# MCU_Connections.net
KiCad netlist of a schematic drawn in Altium Designer
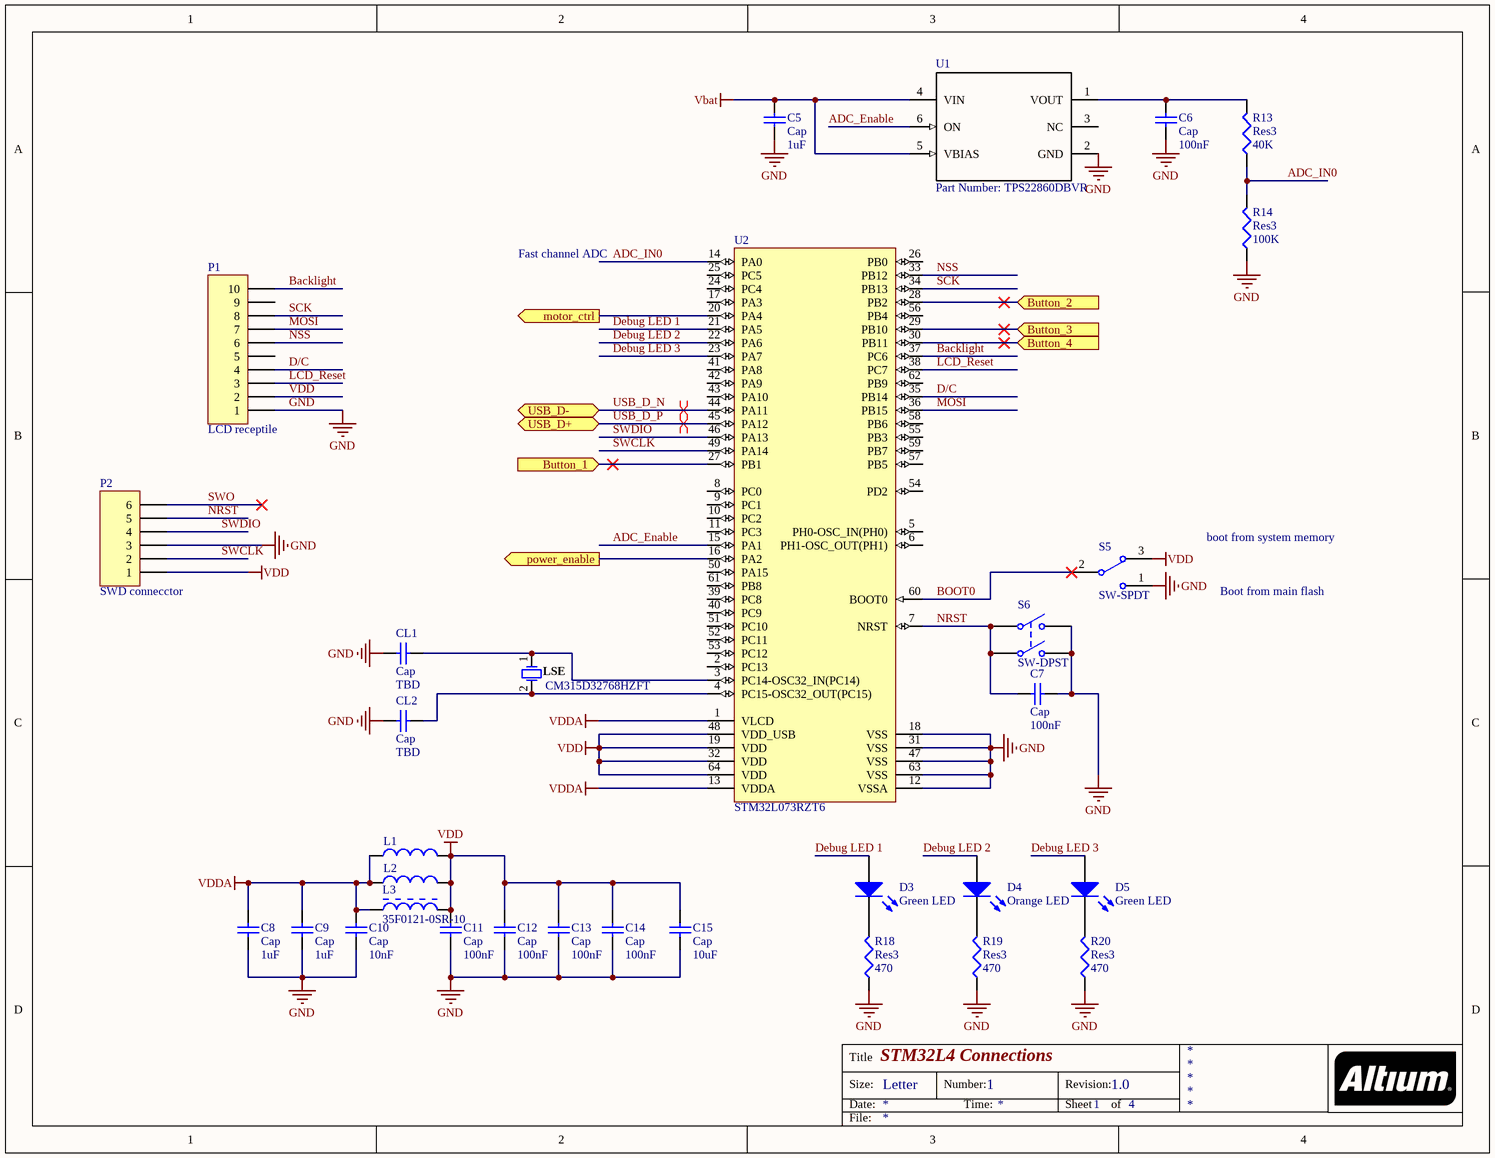
[diagram p0: MCU_Connections.SchDoc]

(export (version "E")
  (design (tool "Eeschema 10.0.6"))
  (components
    (comp (ref "C5")
      (value "Cap")
      (footprint "C0805")
      (description "Capacitor")
      (fields (field (name "ALTIUM_VALUE") "1uF") (field (name "PUBLISHER") "Altium Limited"))
      (libsource (lib "Miscellaneous Devices") (part "Cap"))
    )
    (comp (ref "C6")
      (value "Cap")
      (footprint "C0805")
      (description "Capacitor")
      (fields (field (name "ALTIUM_VALUE") "100nF") (field (name "PUBLISHER") "Altium Limited"))
      (libsource (lib "Miscellaneous Devices") (part "Cap"))
    )
    (comp (ref "C7")
      (value "Cap")
      (footprint "C0805")
      (description "Capacitor")
      (fields (field (name "ALTIUM_VALUE") "100nF") (field (name "PUBLISHER") "Altium Limited"))
      (libsource (lib "Miscellaneous Devices") (part "Cap"))
    )
    (comp (ref "C8")
      (value "Cap")
      (footprint "C0805")
      (description "Capacitor")
      (fields (field (name "ALTIUM_VALUE") "1uF") (field (name "PUBLISHER") "Altium Limited"))
      (libsource (lib "Miscellaneous Devices") (part "Cap"))
    )
    (comp (ref "C9")
      (value "Cap")
      (footprint "C0805")
      (description "Capacitor")
      (fields (field (name "ALTIUM_VALUE") "1uF") (field (name "PUBLISHER") "Altium Limited"))
      (libsource (lib "Miscellaneous Devices") (part "Cap"))
    )
    (comp (ref "C10")
      (value "Cap")
      (footprint "C0805")
      (description "Capacitor")
      (fields (field (name "ALTIUM_VALUE") "10nF") (field (name "PUBLISHER") "Altium Limited"))
      (libsource (lib "Miscellaneous Devices") (part "Cap"))
    )
    (comp (ref "C11")
      (value "Cap")
      (footprint "C0805")
      (description "Capacitor")
      (fields (field (name "ALTIUM_VALUE") "100nF") (field (name "PUBLISHER") "Altium Limited"))
      (libsource (lib "Miscellaneous Devices") (part "Cap"))
    )
    (comp (ref "C12")
      (value "Cap")
      (footprint "C0805")
      (description "Capacitor")
      (fields (field (name "ALTIUM_VALUE") "100nF") (field (name "PUBLISHER") "Altium Limited"))
      (libsource (lib "Miscellaneous Devices") (part "Cap"))
    )
    (comp (ref "C13")
      (value "Cap")
      (footprint "C0805")
      (description "Capacitor")
      (fields (field (name "ALTIUM_VALUE") "100nF") (field (name "PUBLISHER") "Altium Limited"))
      (libsource (lib "Miscellaneous Devices") (part "Cap"))
    )
    (comp (ref "C14")
      (value "Cap")
      (footprint "C0805")
      (description "Capacitor")
      (fields (field (name "ALTIUM_VALUE") "100nF") (field (name "PUBLISHER") "Altium Limited"))
      (libsource (lib "Miscellaneous Devices") (part "Cap"))
    )
    (comp (ref "C15")
      (value "Cap")
      (footprint "C0805")
      (description "Capacitor")
      (fields (field (name "ALTIUM_VALUE") "10uF") (field (name "PUBLISHER") "Altium Limited"))
      (libsource (lib "Miscellaneous Devices") (part "Cap"))
    )
    (comp (ref "CL1")
      (value "Cap")
      (footprint "C0805")
      (description "Capacitor")
      (fields (field (name "ALTIUM_VALUE") "TBD") (field (name "PUBLISHER") "Altium Limited"))
      (libsource (lib "Miscellaneous Devices") (part "Cap"))
    )
    (comp (ref "CL2")
      (value "Cap")
      (footprint "C0805")
      (description "Capacitor")
      (fields (field (name "ALTIUM_VALUE") "TBD") (field (name "PUBLISHER") "Altium Limited"))
      (libsource (lib "Miscellaneous Devices") (part "Cap"))
    )
    (comp (ref "D3")
      (value "Green LED")
      (footprint "3.2X1.6X1.1")
      (description "Typical RED, GREEN, YELLOW, AMBER GaAs LED")
      (fields (field (name "PUBLISHER") "Altium Limited"))
      (libsource (lib "Miscellaneous Devices") (part "LED2"))
    )
    (comp (ref "D4")
      (value "Orange LED")
      (footprint "3.2X1.6X1.1")
      (description "Typical RED, GREEN, YELLOW, AMBER GaAs LED")
      (fields (field (name "PUBLISHER") "Altium Limited"))
      (libsource (lib "Miscellaneous Devices") (part "LED2"))
    )
    (comp (ref "D5")
      (value "Green LED")
      (footprint "3.2X1.6X1.1")
      (description "Typical RED, GREEN, YELLOW, AMBER GaAs LED")
      (fields (field (name "PUBLISHER") "Altium Limited"))
      (libsource (lib "Miscellaneous Devices") (part "LED2"))
    )
    (comp (ref "L1")
      (value "~")
      (footprint "C0805")
      (description "Inductor")
      (fields (field (name "PUBLISHER") "Altium Limited"))
      (libsource (lib "Miscellaneous Devices") (part "Inductor"))
    )
    (comp (ref "L2")
      (value "~")
      (footprint "C1206")
      (description "Inductor")
      (fields (field (name "PUBLISHER") "Altium Limited"))
      (libsource (lib "Miscellaneous Devices") (part "Inductor"))
    )
    (comp (ref "L3")
      (value "35F0121-0SR-10")
      (footprint "LIRD-35F0121-0SR-10_V")
      (description "EMI Filtering & RF Inductor, 10 A, 0.75 mOhm, -40 to 125 degC, 2-Pin SMD, RoHS, Tape and Reel")
      (fields (field (name "MANUFACTURER") "Laird"))
      (libsource (lib "Altium Content Vault") (part "IND-FB-2"))
    )
    (comp (ref "LSE")
      (value "CM315D32768HZFT")
      (footprint "CMHT-CM315D-2_V")
      (fields (field (name "MANUFACTURER") "Citizen Micro HumanTech"))
      (libsource (lib "Altium Content Vault") (part "XTAL-1-2-2"))
    )
    (comp (ref "P1")
      (value "LCD receptile")
      (footprint "HDR1X10")
      (description "Header, 10-Pin")
      (fields (field (name "PUBLISHER") "Altium Limited"))
      (libsource (lib "Miscellaneous Connectors") (part "Header 10"))
    )
    (comp (ref "P2")
      (value "SWD connecctor")
      (footprint "HDR1X6")
      (description "Header, 6-Pin")
      (fields (field (name "PUBLISHER") "Altium Limited"))
      (libsource (lib "Miscellaneous Connectors") (part "Header 6"))
    )
    (comp (ref "R13")
      (value "Res3")
      (footprint "1608[0603]")
      (description "Resistor")
      (fields (field (name "ALTIUM_VALUE") "40K") (field (name "PUBLISHER") "Altium Limited"))
      (libsource (lib "Miscellaneous Devices") (part "Res3"))
    )
    (comp (ref "R14")
      (value "Res3")
      (footprint "1608[0603]")
      (description "Resistor")
      (fields (field (name "ALTIUM_VALUE") "100K") (field (name "PUBLISHER") "Altium Limited"))
      (libsource (lib "Miscellaneous Devices") (part "Res3"))
    )
    (comp (ref "R18")
      (value "Res3")
      (footprint "1608[0603]")
      (description "Resistor")
      (fields (field (name "ALTIUM_VALUE") "470") (field (name "PUBLISHER") "Altium Limited"))
      (libsource (lib "Miscellaneous Devices") (part "Res3"))
    )
    (comp (ref "R19")
      (value "Res3")
      (footprint "1608[0603]")
      (description "Resistor")
      (fields (field (name "ALTIUM_VALUE") "470") (field (name "PUBLISHER") "Altium Limited"))
      (libsource (lib "Miscellaneous Devices") (part "Res3"))
    )
    (comp (ref "R20")
      (value "Res3")
      (footprint "1608[0603]")
      (description "Resistor")
      (fields (field (name "ALTIUM_VALUE") "470") (field (name "PUBLISHER") "Altium Limited"))
      (libsource (lib "Miscellaneous Devices") (part "Res3"))
    )
    (comp (ref "S5")
      (value "SW-SPDT")
      (footprint "HDR1X3")
      (description "SPDT Subminiature Toggle Switch, Right Angle Mounting, Vertical Actuation")
      (fields (field (name "PUBLISHER") "Altium Limited"))
      (libsource (lib "Miscellaneous Devices") (part "SW-SPDT"))
    )
    (comp (ref "S6")
      (value "SW-DPST")
      (footprint "PCBComponent_1")
      (description "Double-Pole, Single-Throw Switch")
      (fields (field (name "PUBLISHER") "Altium Limited"))
      (libsource (lib "Miscellaneous Devices") (part "SW-DPST"))
    )
    (comp (ref "U1")
      (value "Part Number: TPS22860DBVR")
      (footprint "DBV0006A_N")
      (description "No Description Available")
      (fields
        (field (name "MANUFACTURER_PART_NUMBER") "TPS22860DBVR")
        (field (name "MANUFACTURER") "Texas Instruments")
        (field (name "COPYRIGHT") "Copyright (C) 2018 Accelerated Designs. All rights reserved")
      )
      (libsource (lib "TI-TPS22860DBVR") (part "TPS22860DBVR"))
    )
    (comp (ref "U2")
      (value "STM32L073RZT6")
      (footprint "STM-LQFP64_M")
      (libsource (lib "Altium Content Vault") (part "MC-ARM-STM32L073-LQFP64"))
    )
  )
  (nets
    (net (code "1") (name "/ADC_Enable") (class "Default")
      (node (ref "U1") (pin "6") (pinfunction "ON_6") (pintype "input"))
      (node (ref "U2") (pin "15") (pinfunction "PA1_15") (pintype "bidirectional"))
    )
    (net (code "2") (name "/ADC_IN0") (class "Default")
      (node (ref "R13") (pin "1") (pinfunction "1_1") (pintype "passive"))
      (node (ref "R14") (pin "2") (pinfunction "2_2") (pintype "passive"))
      (node (ref "U2") (pin "14") (pinfunction "PA0_14") (pintype "bidirectional"))
    )
    (net (code "3") (name "/BOOT0") (class "Default")
      (node (ref "S5") (pin "2") (pinfunction "2_2") (pintype "passive"))
      (node (ref "U2") (pin "60") (pinfunction "BOOT0_60") (pintype "input"))
    )
    (net (code "4") (name "/Backlight") (class "Default")
      (node (ref "P1") (pin "10") (pinfunction "10_10") (pintype "passive"))
      (node (ref "U2") (pin "37") (pinfunction "PC6_37") (pintype "bidirectional"))
    )
    (net (code "5") (name "/Button_1") (class "Default")
      (node (ref "U2") (pin "27") (pinfunction "PB1_27") (pintype "bidirectional"))
    )
    (net (code "6") (name "/Button_2") (class "Default")
      (node (ref "U2") (pin "28") (pinfunction "PB2_28") (pintype "bidirectional"))
    )
    (net (code "7") (name "/Button_3") (class "Default")
      (node (ref "U2") (pin "29") (pinfunction "PB10_29") (pintype "bidirectional"))
    )
    (net (code "8") (name "/Button_4") (class "Default")
      (node (ref "U2") (pin "30") (pinfunction "PB11_30") (pintype "bidirectional"))
    )
    (net (code "9") (name "/Debug LED 1") (class "Default")
      (node (ref "D3") (pin "1") (pinfunction "A_1") (pintype "passive"))
      (node (ref "U2") (pin "21") (pinfunction "PA5_21") (pintype "bidirectional"))
    )
    (net (code "10") (name "/Debug LED 2") (class "Default")
      (node (ref "D4") (pin "1") (pinfunction "A_1") (pintype "passive"))
      (node (ref "U2") (pin "22") (pinfunction "PA6_22") (pintype "bidirectional"))
    )
    (net (code "11") (name "/Debug LED 3") (class "Default")
      (node (ref "D5") (pin "1") (pinfunction "A_1") (pintype "passive"))
      (node (ref "U2") (pin "23") (pinfunction "PA7_23") (pintype "bidirectional"))
    )
    (net (code "12") (name "/D{slash}C") (class "Default")
      (node (ref "P1") (pin "4") (pinfunction "4_4") (pintype "passive"))
      (node (ref "U2") (pin "35") (pinfunction "PB14_35") (pintype "bidirectional"))
    )
    (net (code "13") (name "/LCD_Reset") (class "Default")
      (node (ref "P1") (pin "3") (pinfunction "3_3") (pintype "passive"))
      (node (ref "U2") (pin "38") (pinfunction "PC7_38") (pintype "bidirectional"))
    )
    (net (code "14") (name "/MOSI") (class "Default")
      (node (ref "P1") (pin "7") (pinfunction "7_7") (pintype "passive"))
      (node (ref "U2") (pin "36") (pinfunction "PB15_36") (pintype "bidirectional"))
    )
    (net (code "15") (name "/NRST") (class "Default")
      (node (ref "C7") (pin "1") (pinfunction "1_1") (pintype "passive"))
      (node (ref "P2") (pin "5") (pinfunction "5_5") (pintype "passive"))
      (node (ref "S6") (pin "1") (pinfunction "COMMON1_1") (pintype "passive"))
      (node (ref "S6") (pin "3") (pinfunction "COMMON2_3") (pintype "passive"))
      (node (ref "U2") (pin "7") (pinfunction "NRST_7") (pintype "bidirectional"))
    )
    (net (code "16") (name "/NSS") (class "Default")
      (node (ref "P1") (pin "6") (pinfunction "6_6") (pintype "passive"))
      (node (ref "U2") (pin "33") (pinfunction "PB12_33") (pintype "bidirectional"))
    )
    (net (code "17") (name "/SCK") (class "Default")
      (node (ref "P1") (pin "8") (pinfunction "8_8") (pintype "passive"))
      (node (ref "U2") (pin "34") (pinfunction "PB13_34") (pintype "bidirectional"))
    )
    (net (code "18") (name "/SWCLK") (class "Default")
      (node (ref "P2") (pin "2") (pinfunction "2_2") (pintype "passive"))
      (node (ref "U2") (pin "49") (pinfunction "PA14_49") (pintype "bidirectional"))
    )
    (net (code "19") (name "/SWDIO") (class "Default")
      (node (ref "P2") (pin "4") (pinfunction "4_4") (pintype "passive"))
      (node (ref "U2") (pin "46") (pinfunction "PA13_46") (pintype "bidirectional"))
    )
    (net (code "20") (name "/SWO") (class "Default")
      (node (ref "P2") (pin "6") (pinfunction "6_6") (pintype "passive+no_connect"))
    )
    (net (code "21") (name "/USB_D_N") (class "Default")
      (node (ref "U2") (pin "44") (pinfunction "PA11_44") (pintype "bidirectional"))
    )
    (net (code "22") (name "/USB_D_P") (class "Default")
      (node (ref "U2") (pin "45") (pinfunction "PA12_45") (pintype "bidirectional"))
    )
    (net (code "23") (name "/motor_ctrl") (class "Default")
      (node (ref "U2") (pin "20") (pinfunction "PA4_20") (pintype "bidirectional"))
    )
    (net (code "24") (name "/power_enable") (class "Default")
      (node (ref "U2") (pin "16") (pinfunction "PA2_16") (pintype "bidirectional"))
    )
    (net (code "25") (name "GND") (class "Default")
      (node (ref "C10") (pin "1") (pinfunction "1_1") (pintype "passive"))
      (node (ref "C11") (pin "1") (pinfunction "1_1") (pintype "passive"))
      (node (ref "C12") (pin "1") (pinfunction "1_1") (pintype "passive"))
      (node (ref "C13") (pin "1") (pinfunction "1_1") (pintype "passive"))
      (node (ref "C14") (pin "1") (pinfunction "1_1") (pintype "passive"))
      (node (ref "C15") (pin "1") (pinfunction "1_1") (pintype "passive"))
      (node (ref "C5") (pin "1") (pinfunction "1_1") (pintype "passive"))
      (node (ref "C6") (pin "1") (pinfunction "1_1") (pintype "passive"))
      (node (ref "C7") (pin "2") (pinfunction "2_2") (pintype "passive"))
      (node (ref "C8") (pin "1") (pinfunction "1_1") (pintype "passive"))
      (node (ref "C9") (pin "1") (pinfunction "1_1") (pintype "passive"))
      (node (ref "CL1") (pin "1") (pinfunction "1_1") (pintype "passive"))
      (node (ref "CL2") (pin "1") (pinfunction "1_1") (pintype "passive"))
      (node (ref "P1") (pin "1") (pinfunction "1_1") (pintype "passive"))
      (node (ref "P2") (pin "3") (pinfunction "3_3") (pintype "passive"))
      (node (ref "R14") (pin "1") (pinfunction "1_1") (pintype "passive"))
      (node (ref "R18") (pin "1") (pinfunction "1_1") (pintype "passive"))
      (node (ref "R19") (pin "1") (pinfunction "1_1") (pintype "passive"))
      (node (ref "R20") (pin "1") (pinfunction "1_1") (pintype "passive"))
      (node (ref "S5") (pin "1") (pinfunction "1_1") (pintype "passive"))
      (node (ref "S6") (pin "2") (pinfunction "NO1_2") (pintype "passive"))
      (node (ref "S6") (pin "4") (pinfunction "NO2_4") (pintype "passive"))
      (node (ref "U1") (pin "2") (pinfunction "GND_2") (pintype "power_in"))
      (node (ref "U2") (pin "12") (pinfunction "VSSA_12") (pintype "power_in"))
      (node (ref "U2") (pin "18") (pinfunction "VSS_18") (pintype "power_in"))
      (node (ref "U2") (pin "31") (pinfunction "VSS_31") (pintype "power_in"))
      (node (ref "U2") (pin "47") (pinfunction "VSS_47") (pintype "power_in"))
      (node (ref "U2") (pin "63") (pinfunction "VSS_63") (pintype "power_in"))
    )
    (net (code "26") (name "Net-(D3-K)") (class "Default")
      (node (ref "D3") (pin "2") (pinfunction "K_2") (pintype "passive"))
      (node (ref "R18") (pin "2") (pinfunction "2_2") (pintype "passive"))
    )
    (net (code "27") (name "Net-(D4-K)") (class "Default")
      (node (ref "D4") (pin "2") (pinfunction "K_2") (pintype "passive"))
      (node (ref "R19") (pin "2") (pinfunction "2_2") (pintype "passive"))
    )
    (net (code "28") (name "Net-(D5-K)") (class "Default")
      (node (ref "D5") (pin "2") (pinfunction "K_2") (pintype "passive"))
      (node (ref "R20") (pin "2") (pinfunction "2_2") (pintype "passive"))
    )
    (net (code "29") (name "Net-(U1-VOUT)") (class "Default")
      (node (ref "C6") (pin "2") (pinfunction "2_2") (pintype "passive"))
      (node (ref "R13") (pin "2") (pinfunction "2_2") (pintype "passive"))
      (node (ref "U1") (pin "1") (pinfunction "VOUT_1") (pintype "power_in"))
    )
    (net (code "30") (name "Net-(U2-PC14-OSC32_IN(PC14))") (class "Default")
      (node (ref "CL1") (pin "2") (pinfunction "2_2") (pintype "passive"))
      (node (ref "LSE") (pin "1") (pinfunction "1_1") (pintype "passive"))
      (node (ref "U2") (pin "3") (pinfunction "PC14-OSC32_IN(PC14)_3") (pintype "bidirectional"))
    )
    (net (code "31") (name "Net-(U2-PC15-OSC32_OUT(PC15))") (class "Default")
      (node (ref "CL2") (pin "2") (pinfunction "2_2") (pintype "passive"))
      (node (ref "LSE") (pin "2") (pinfunction "2_2") (pintype "passive"))
      (node (ref "U2") (pin "4") (pinfunction "PC15-OSC32_OUT(PC15)_4") (pintype "bidirectional"))
    )
    (net (code "32") (name "VDD") (class "Default")
      (node (ref "C11") (pin "2") (pinfunction "2_2") (pintype "passive"))
      (node (ref "C12") (pin "2") (pinfunction "2_2") (pintype "passive"))
      (node (ref "C13") (pin "2") (pinfunction "2_2") (pintype "passive"))
      (node (ref "C14") (pin "2") (pinfunction "2_2") (pintype "passive"))
      (node (ref "C15") (pin "2") (pinfunction "2_2") (pintype "passive"))
      (node (ref "L1") (pin "2") (pinfunction "2_2") (pintype "passive"))
      (node (ref "L2") (pin "2") (pinfunction "2_2") (pintype "passive"))
      (node (ref "L3") (pin "2") (pinfunction "2_2") (pintype "passive"))
      (node (ref "P1") (pin "2") (pinfunction "2_2") (pintype "passive"))
      (node (ref "P2") (pin "1") (pinfunction "1_1") (pintype "passive"))
      (node (ref "S5") (pin "3") (pinfunction "3_3") (pintype "passive"))
      (node (ref "U2") (pin "19") (pinfunction "VDD_19") (pintype "power_in"))
      (node (ref "U2") (pin "32") (pinfunction "VDD_32") (pintype "power_in"))
      (node (ref "U2") (pin "48") (pinfunction "VDD_USB_48") (pintype "power_in"))
      (node (ref "U2") (pin "64") (pinfunction "VDD_64") (pintype "power_in"))
    )
    (net (code "33") (name "VDDA") (class "Default")
      (node (ref "C10") (pin "2") (pinfunction "2_2") (pintype "passive"))
      (node (ref "C8") (pin "2") (pinfunction "2_2") (pintype "passive"))
      (node (ref "C9") (pin "2") (pinfunction "2_2") (pintype "passive"))
      (node (ref "L1") (pin "1") (pinfunction "1_1") (pintype "passive"))
      (node (ref "L2") (pin "1") (pinfunction "1_1") (pintype "passive"))
      (node (ref "L3") (pin "1") (pinfunction "1_1") (pintype "passive"))
      (node (ref "U2") (pin "1") (pinfunction "VLCD_1") (pintype "power_in"))
      (node (ref "U2") (pin "13") (pinfunction "VDDA_13") (pintype "power_in"))
    )
    (net (code "34") (name "Vbat") (class "Default")
      (node (ref "C5") (pin "2") (pinfunction "2_2") (pintype "passive"))
      (node (ref "U1") (pin "4") (pinfunction "VIN_4") (pintype "power_in"))
      (node (ref "U1") (pin "5") (pinfunction "VBIAS_5") (pintype "input"))
    )
    (net (code "35") (name "unconnected-(P1-Pad5)") (class "Default")
      (node (ref "P1") (pin "5") (pinfunction "5_5") (pintype "passive"))
    )
    (net (code "36") (name "unconnected-(P1-Pad9)") (class "Default")
      (node (ref "P1") (pin "9") (pinfunction "9_9") (pintype "passive"))
    )
    (net (code "37") (name "unconnected-(U1-NC-Pad3)") (class "Default")
      (node (ref "U1") (pin "3") (pinfunction "NC_3") (pintype "passive"))
    )
    (net (code "38") (name "unconnected-(U2-PA3-Pad17)") (class "Default")
      (node (ref "U2") (pin "17") (pinfunction "PA3_17") (pintype "bidirectional"))
    )
    (net (code "39") (name "unconnected-(U2-PA8-Pad41)") (class "Default")
      (node (ref "U2") (pin "41") (pinfunction "PA8_41") (pintype "bidirectional"))
    )
    (net (code "40") (name "unconnected-(U2-PA9-Pad42)") (class "Default")
      (node (ref "U2") (pin "42") (pinfunction "PA9_42") (pintype "bidirectional"))
    )
    (net (code "41") (name "unconnected-(U2-PA10-Pad43)") (class "Default")
      (node (ref "U2") (pin "43") (pinfunction "PA10_43") (pintype "bidirectional"))
    )
    (net (code "42") (name "unconnected-(U2-PA15-Pad50)") (class "Default")
      (node (ref "U2") (pin "50") (pinfunction "PA15_50") (pintype "bidirectional"))
    )
    (net (code "43") (name "unconnected-(U2-PB0-Pad26)") (class "Default")
      (node (ref "U2") (pin "26") (pinfunction "PB0_26") (pintype "bidirectional"))
    )
    (net (code "44") (name "unconnected-(U2-PB3-Pad55)") (class "Default")
      (node (ref "U2") (pin "55") (pinfunction "PB3_55") (pintype "bidirectional"))
    )
    (net (code "45") (name "unconnected-(U2-PB4-Pad56)") (class "Default")
      (node (ref "U2") (pin "56") (pinfunction "PB4_56") (pintype "bidirectional"))
    )
    (net (code "46") (name "unconnected-(U2-PB5-Pad57)") (class "Default")
      (node (ref "U2") (pin "57") (pinfunction "PB5_57") (pintype "bidirectional"))
    )
    (net (code "47") (name "unconnected-(U2-PB6-Pad58)") (class "Default")
      (node (ref "U2") (pin "58") (pinfunction "PB6_58") (pintype "bidirectional"))
    )
    (net (code "48") (name "unconnected-(U2-PB7-Pad59)") (class "Default")
      (node (ref "U2") (pin "59") (pinfunction "PB7_59") (pintype "bidirectional"))
    )
    (net (code "49") (name "unconnected-(U2-PB8-Pad61)") (class "Default")
      (node (ref "U2") (pin "61") (pinfunction "PB8_61") (pintype "bidirectional"))
    )
    (net (code "50") (name "unconnected-(U2-PB9-Pad62)") (class "Default")
      (node (ref "U2") (pin "62") (pinfunction "PB9_62") (pintype "bidirectional"))
    )
    (net (code "51") (name "unconnected-(U2-PC0-Pad8)") (class "Default")
      (node (ref "U2") (pin "8") (pinfunction "PC0_8") (pintype "bidirectional"))
    )
    (net (code "52") (name "unconnected-(U2-PC1-Pad9)") (class "Default")
      (node (ref "U2") (pin "9") (pinfunction "PC1_9") (pintype "bidirectional"))
    )
    (net (code "53") (name "unconnected-(U2-PC2-Pad10)") (class "Default")
      (node (ref "U2") (pin "10") (pinfunction "PC2_10") (pintype "bidirectional"))
    )
    (net (code "54") (name "unconnected-(U2-PC3-Pad11)") (class "Default")
      (node (ref "U2") (pin "11") (pinfunction "PC3_11") (pintype "bidirectional"))
    )
    (net (code "55") (name "unconnected-(U2-PC4-Pad24)") (class "Default")
      (node (ref "U2") (pin "24") (pinfunction "PC4_24") (pintype "bidirectional"))
    )
    (net (code "56") (name "unconnected-(U2-PC5-Pad25)") (class "Default")
      (node (ref "U2") (pin "25") (pinfunction "PC5_25") (pintype "bidirectional"))
    )
    (net (code "57") (name "unconnected-(U2-PC8-Pad39)") (class "Default")
      (node (ref "U2") (pin "39") (pinfunction "PC8_39") (pintype "bidirectional"))
    )
    (net (code "58") (name "unconnected-(U2-PC9-Pad40)") (class "Default")
      (node (ref "U2") (pin "40") (pinfunction "PC9_40") (pintype "bidirectional"))
    )
    (net (code "59") (name "unconnected-(U2-PC10-Pad51)") (class "Default")
      (node (ref "U2") (pin "51") (pinfunction "PC10_51") (pintype "bidirectional"))
    )
    (net (code "60") (name "unconnected-(U2-PC11-Pad52)") (class "Default")
      (node (ref "U2") (pin "52") (pinfunction "PC11_52") (pintype "bidirectional"))
    )
    (net (code "61") (name "unconnected-(U2-PC12-Pad53)") (class "Default")
      (node (ref "U2") (pin "53") (pinfunction "PC12_53") (pintype "bidirectional"))
    )
    (net (code "62") (name "unconnected-(U2-PC13-Pad2)") (class "Default")
      (node (ref "U2") (pin "2") (pinfunction "PC13_2") (pintype "bidirectional"))
    )
    (net (code "63") (name "unconnected-(U2-PD2-Pad54)") (class "Default")
      (node (ref "U2") (pin "54") (pinfunction "PD2_54") (pintype "bidirectional"))
    )
    (net (code "64") (name "unconnected-(U2-PH0-OSC_IN(PH0)-Pad5)") (class "Default")
      (node (ref "U2") (pin "5") (pinfunction "PH0-OSC_IN(PH0)_5") (pintype "bidirectional"))
    )
    (net (code "65") (name "unconnected-(U2-PH1-OSC_OUT(PH1)-Pad6)") (class "Default")
      (node (ref "U2") (pin "6") (pinfunction "PH1-OSC_OUT(PH1)_6") (pintype "bidirectional"))
    )
  )
)
